# eBay1.net
KiCad netlist of a schematic drawn in EAGLE
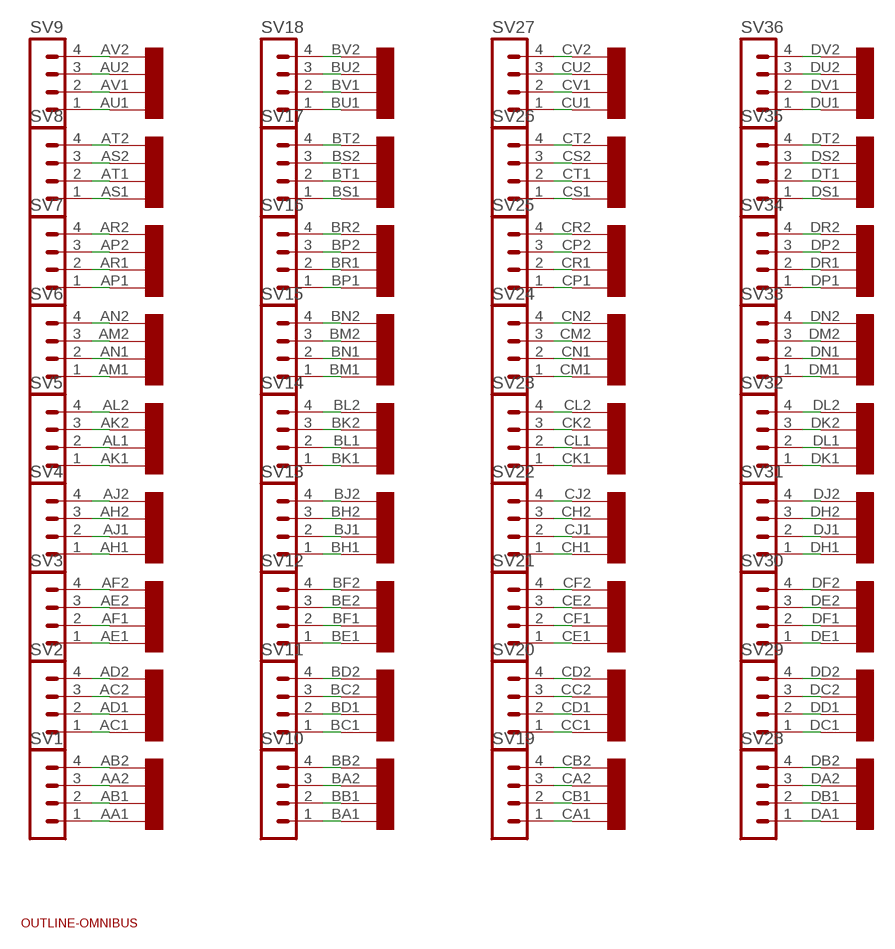
[diagram p0: schematic, sheet 1]

(export (version "E")
  (design (tool "Eeschema 10.0.6"))
  (components
    (comp (ref "SV1")
      (value "MA04-1")
      (footprint "eagle-import:MA04-1")
      (libsource (lib "eagle-import") (part "MA04-1"))
    )
    (comp (ref "SV2")
      (value "MA04-1")
      (footprint "eagle-import:MA04-1")
      (libsource (lib "eagle-import") (part "MA04-1"))
    )
    (comp (ref "SV3")
      (value "MA04-1")
      (footprint "eagle-import:MA04-1")
      (libsource (lib "eagle-import") (part "MA04-1"))
    )
    (comp (ref "SV4")
      (value "MA04-1")
      (footprint "eagle-import:MA04-1")
      (libsource (lib "eagle-import") (part "MA04-1"))
    )
    (comp (ref "SV5")
      (value "MA04-1")
      (footprint "eagle-import:MA04-1")
      (libsource (lib "eagle-import") (part "MA04-1"))
    )
    (comp (ref "SV6")
      (value "MA04-1")
      (footprint "eagle-import:MA04-1")
      (libsource (lib "eagle-import") (part "MA04-1"))
    )
    (comp (ref "SV7")
      (value "MA04-1")
      (footprint "eagle-import:MA04-1")
      (libsource (lib "eagle-import") (part "MA04-1"))
    )
    (comp (ref "SV8")
      (value "MA04-1")
      (footprint "eagle-import:MA04-1")
      (libsource (lib "eagle-import") (part "MA04-1"))
    )
    (comp (ref "SV9")
      (value "MA04-1")
      (footprint "eagle-import:MA04-1")
      (libsource (lib "eagle-import") (part "MA04-1"))
    )
    (comp (ref "SV10")
      (value "MA04-1")
      (footprint "eagle-import:MA04-1")
      (libsource (lib "eagle-import") (part "MA04-1"))
    )
    (comp (ref "SV11")
      (value "MA04-1")
      (footprint "eagle-import:MA04-1")
      (libsource (lib "eagle-import") (part "MA04-1"))
    )
    (comp (ref "SV12")
      (value "MA04-1")
      (footprint "eagle-import:MA04-1")
      (libsource (lib "eagle-import") (part "MA04-1"))
    )
    (comp (ref "SV13")
      (value "MA04-1")
      (footprint "eagle-import:MA04-1")
      (libsource (lib "eagle-import") (part "MA04-1"))
    )
    (comp (ref "SV14")
      (value "MA04-1")
      (footprint "eagle-import:MA04-1")
      (libsource (lib "eagle-import") (part "MA04-1"))
    )
    (comp (ref "SV15")
      (value "MA04-1")
      (footprint "eagle-import:MA04-1")
      (libsource (lib "eagle-import") (part "MA04-1"))
    )
    (comp (ref "SV16")
      (value "MA04-1")
      (footprint "eagle-import:MA04-1")
      (libsource (lib "eagle-import") (part "MA04-1"))
    )
    (comp (ref "SV17")
      (value "MA04-1")
      (footprint "eagle-import:MA04-1")
      (libsource (lib "eagle-import") (part "MA04-1"))
    )
    (comp (ref "SV18")
      (value "MA04-1")
      (footprint "eagle-import:MA04-1")
      (libsource (lib "eagle-import") (part "MA04-1"))
    )
    (comp (ref "SV19")
      (value "MA04-1")
      (footprint "eagle-import:MA04-1")
      (libsource (lib "eagle-import") (part "MA04-1"))
    )
    (comp (ref "SV20")
      (value "MA04-1")
      (footprint "eagle-import:MA04-1")
      (libsource (lib "eagle-import") (part "MA04-1"))
    )
    (comp (ref "SV21")
      (value "MA04-1")
      (footprint "eagle-import:MA04-1")
      (libsource (lib "eagle-import") (part "MA04-1"))
    )
    (comp (ref "SV22")
      (value "MA04-1")
      (footprint "eagle-import:MA04-1")
      (libsource (lib "eagle-import") (part "MA04-1"))
    )
    (comp (ref "SV23")
      (value "MA04-1")
      (footprint "eagle-import:MA04-1")
      (libsource (lib "eagle-import") (part "MA04-1"))
    )
    (comp (ref "SV24")
      (value "MA04-1")
      (footprint "eagle-import:MA04-1")
      (libsource (lib "eagle-import") (part "MA04-1"))
    )
    (comp (ref "SV25")
      (value "MA04-1")
      (footprint "eagle-import:MA04-1")
      (libsource (lib "eagle-import") (part "MA04-1"))
    )
    (comp (ref "SV26")
      (value "MA04-1")
      (footprint "eagle-import:MA04-1")
      (libsource (lib "eagle-import") (part "MA04-1"))
    )
    (comp (ref "SV27")
      (value "MA04-1")
      (footprint "eagle-import:MA04-1")
      (libsource (lib "eagle-import") (part "MA04-1"))
    )
    (comp (ref "SV28")
      (value "MA04-1")
      (footprint "eagle-import:MA04-1")
      (libsource (lib "eagle-import") (part "MA04-1"))
    )
    (comp (ref "SV29")
      (value "MA04-1")
      (footprint "eagle-import:MA04-1")
      (libsource (lib "eagle-import") (part "MA04-1"))
    )
    (comp (ref "SV30")
      (value "MA04-1")
      (footprint "eagle-import:MA04-1")
      (libsource (lib "eagle-import") (part "MA04-1"))
    )
    (comp (ref "SV31")
      (value "MA04-1")
      (footprint "eagle-import:MA04-1")
      (libsource (lib "eagle-import") (part "MA04-1"))
    )
    (comp (ref "SV32")
      (value "MA04-1")
      (footprint "eagle-import:MA04-1")
      (libsource (lib "eagle-import") (part "MA04-1"))
    )
    (comp (ref "SV33")
      (value "MA04-1")
      (footprint "eagle-import:MA04-1")
      (libsource (lib "eagle-import") (part "MA04-1"))
    )
    (comp (ref "SV34")
      (value "MA04-1")
      (footprint "eagle-import:MA04-1")
      (libsource (lib "eagle-import") (part "MA04-1"))
    )
    (comp (ref "SV35")
      (value "MA04-1")
      (footprint "eagle-import:MA04-1")
      (libsource (lib "eagle-import") (part "MA04-1"))
    )
    (comp (ref "SV36")
      (value "MA04-1")
      (footprint "eagle-import:MA04-1")
      (libsource (lib "eagle-import") (part "MA04-1"))
    )
    (comp (ref "U$1")
      (value "OUTLINE-OMNIBUS")
      (footprint "eagle-import:OMNIBUS")
      (libsource (lib "eagle-import") (part "OUTLINE-OMNIBUS"))
    )
    (comp (ref "U$2")
      (value "QUAD")
      (footprint "eagle-import:EDGE-CON8")
      (libsource (lib "eagle-import") (part "QUAD"))
    )
  )
  (nets
    (net (code "1") (name "Net-(U$2A-1)") (class "Default")
      (node (ref "SV1") (pin "1") (pinfunction "1_1") (pintype "passive"))
      (node (ref "U$2") (pin "AA1") (pinfunction "1_AA1") (pintype "bidirectional"))
    )
    (net (code "2") (name "Net-(U$2AA-1)") (class "Default")
      (node (ref "SV7") (pin "2") (pinfunction "2_2") (pintype "passive"))
      (node (ref "U$2") (pin "AR1") (pinfunction "1_AR1") (pintype "bidirectional"))
    )
    (net (code "3") (name "Net-(U$2AB-1)") (class "Default")
      (node (ref "SV7") (pin "4") (pinfunction "4_4") (pintype "passive"))
      (node (ref "U$2") (pin "AR2") (pinfunction "1_AR2") (pintype "bidirectional"))
    )
    (net (code "4") (name "Net-(U$2AC-1)") (class "Default")
      (node (ref "SV8") (pin "1") (pinfunction "1_1") (pintype "passive"))
      (node (ref "U$2") (pin "AS1") (pinfunction "1_AS1") (pintype "bidirectional"))
    )
    (net (code "5") (name "Net-(U$2AD-1)") (class "Default")
      (node (ref "SV8") (pin "3") (pinfunction "3_3") (pintype "passive"))
      (node (ref "U$2") (pin "AS2") (pinfunction "1_AS2") (pintype "bidirectional"))
    )
    (net (code "6") (name "Net-(U$2AE-1)") (class "Default")
      (node (ref "SV8") (pin "2") (pinfunction "2_2") (pintype "passive"))
      (node (ref "U$2") (pin "AT1") (pinfunction "1_AT1") (pintype "bidirectional"))
    )
    (net (code "7") (name "Net-(U$2AF-1)") (class "Default")
      (node (ref "SV8") (pin "4") (pinfunction "4_4") (pintype "passive"))
      (node (ref "U$2") (pin "AT2") (pinfunction "1_AT2") (pintype "bidirectional"))
    )
    (net (code "8") (name "Net-(U$2AG-1)") (class "Default")
      (node (ref "SV9") (pin "1") (pinfunction "1_1") (pintype "passive"))
      (node (ref "U$2") (pin "AU1") (pinfunction "1_AU1") (pintype "bidirectional"))
    )
    (net (code "9") (name "Net-(U$2AH-1)") (class "Default")
      (node (ref "SV9") (pin "3") (pinfunction "3_3") (pintype "passive"))
      (node (ref "U$2") (pin "AU2") (pinfunction "1_AU2") (pintype "bidirectional"))
    )
    (net (code "10") (name "Net-(U$2AI-1)") (class "Default")
      (node (ref "SV9") (pin "2") (pinfunction "2_2") (pintype "passive"))
      (node (ref "U$2") (pin "AV1") (pinfunction "1_AV1") (pintype "bidirectional"))
    )
    (net (code "11") (name "Net-(U$2AJ-1)") (class "Default")
      (node (ref "SV9") (pin "4") (pinfunction "4_4") (pintype "passive"))
      (node (ref "U$2") (pin "AV2") (pinfunction "1_AV2") (pintype "bidirectional"))
    )
    (net (code "12") (name "Net-(U$2AK-1)") (class "Default")
      (node (ref "SV10") (pin "1") (pinfunction "1_1") (pintype "passive"))
      (node (ref "U$2") (pin "BA1") (pinfunction "1_BA1") (pintype "bidirectional"))
    )
    (net (code "13") (name "Net-(U$2AL-1)") (class "Default")
      (node (ref "SV10") (pin "3") (pinfunction "3_3") (pintype "passive"))
      (node (ref "U$2") (pin "BA2") (pinfunction "1_BA2") (pintype "bidirectional"))
    )
    (net (code "14") (name "Net-(U$2AM-1)") (class "Default")
      (node (ref "SV10") (pin "2") (pinfunction "2_2") (pintype "passive"))
      (node (ref "U$2") (pin "BB1") (pinfunction "1_BB1") (pintype "bidirectional"))
    )
    (net (code "15") (name "Net-(U$2AN-1)") (class "Default")
      (node (ref "SV10") (pin "4") (pinfunction "4_4") (pintype "passive"))
      (node (ref "U$2") (pin "BB2") (pinfunction "1_BB2") (pintype "bidirectional"))
    )
    (net (code "16") (name "Net-(U$2AO-1)") (class "Default")
      (node (ref "SV11") (pin "1") (pinfunction "1_1") (pintype "passive"))
      (node (ref "U$2") (pin "BC1") (pinfunction "1_BC1") (pintype "bidirectional"))
    )
    (net (code "17") (name "Net-(U$2AP-1)") (class "Default")
      (node (ref "SV11") (pin "3") (pinfunction "3_3") (pintype "passive"))
      (node (ref "U$2") (pin "BC2") (pinfunction "1_BC2") (pintype "bidirectional"))
    )
    (net (code "18") (name "Net-(U$2AQ-1)") (class "Default")
      (node (ref "SV11") (pin "2") (pinfunction "2_2") (pintype "passive"))
      (node (ref "U$2") (pin "BD1") (pinfunction "1_BD1") (pintype "bidirectional"))
    )
    (net (code "19") (name "Net-(U$2AR-1)") (class "Default")
      (node (ref "SV11") (pin "4") (pinfunction "4_4") (pintype "passive"))
      (node (ref "U$2") (pin "BD2") (pinfunction "1_BD2") (pintype "bidirectional"))
    )
    (net (code "20") (name "Net-(U$2AS-1)") (class "Default")
      (node (ref "SV12") (pin "1") (pinfunction "1_1") (pintype "passive"))
      (node (ref "U$2") (pin "BE1") (pinfunction "1_BE1") (pintype "bidirectional"))
    )
    (net (code "21") (name "Net-(U$2AT-1)") (class "Default")
      (node (ref "SV12") (pin "3") (pinfunction "3_3") (pintype "passive"))
      (node (ref "U$2") (pin "BE2") (pinfunction "1_BE2") (pintype "bidirectional"))
    )
    (net (code "22") (name "Net-(U$2AU-1)") (class "Default")
      (node (ref "SV12") (pin "2") (pinfunction "2_2") (pintype "passive"))
      (node (ref "U$2") (pin "BF1") (pinfunction "1_BF1") (pintype "bidirectional"))
    )
    (net (code "23") (name "Net-(U$2AV-1)") (class "Default")
      (node (ref "SV12") (pin "4") (pinfunction "4_4") (pintype "passive"))
      (node (ref "U$2") (pin "BF2") (pinfunction "1_BF2") (pintype "bidirectional"))
    )
    (net (code "24") (name "Net-(U$2AW-1)") (class "Default")
      (node (ref "SV13") (pin "1") (pinfunction "1_1") (pintype "passive"))
      (node (ref "U$2") (pin "BH1") (pinfunction "1_BH1") (pintype "bidirectional"))
    )
    (net (code "25") (name "Net-(U$2AX-1)") (class "Default")
      (node (ref "SV13") (pin "3") (pinfunction "3_3") (pintype "passive"))
      (node (ref "U$2") (pin "BH2") (pinfunction "1_BH2") (pintype "bidirectional"))
    )
    (net (code "26") (name "Net-(U$2AY-1)") (class "Default")
      (node (ref "SV13") (pin "2") (pinfunction "2_2") (pintype "passive"))
      (node (ref "U$2") (pin "BJ1") (pinfunction "1_BJ1") (pintype "bidirectional"))
    )
    (net (code "27") (name "Net-(U$2AZ-1)") (class "Default")
      (node (ref "SV13") (pin "4") (pinfunction "4_4") (pintype "passive"))
      (node (ref "U$2") (pin "BJ2") (pinfunction "1_BJ2") (pintype "bidirectional"))
    )
    (net (code "28") (name "Net-(U$2B-1)") (class "Default")
      (node (ref "SV1") (pin "3") (pinfunction "3_3") (pintype "passive"))
      (node (ref "U$2") (pin "AA2") (pinfunction "1_AA2") (pintype "bidirectional"))
    )
    (net (code "29") (name "Net-(U$2BA-1)") (class "Default")
      (node (ref "SV14") (pin "1") (pinfunction "1_1") (pintype "passive"))
      (node (ref "U$2") (pin "BK1") (pinfunction "1_BK1") (pintype "bidirectional"))
    )
    (net (code "30") (name "Net-(U$2BB-1)") (class "Default")
      (node (ref "SV14") (pin "3") (pinfunction "3_3") (pintype "passive"))
      (node (ref "U$2") (pin "BK2") (pinfunction "1_BK2") (pintype "bidirectional"))
    )
    (net (code "31") (name "Net-(U$2BC-1)") (class "Default")
      (node (ref "SV14") (pin "2") (pinfunction "2_2") (pintype "passive"))
      (node (ref "U$2") (pin "BL1") (pinfunction "1_BL1") (pintype "bidirectional"))
    )
    (net (code "32") (name "Net-(U$2BD-1)") (class "Default")
      (node (ref "SV14") (pin "4") (pinfunction "4_4") (pintype "passive"))
      (node (ref "U$2") (pin "BL2") (pinfunction "1_BL2") (pintype "bidirectional"))
    )
    (net (code "33") (name "Net-(U$2BE-1)") (class "Default")
      (node (ref "SV15") (pin "1") (pinfunction "1_1") (pintype "passive"))
      (node (ref "U$2") (pin "BM1") (pinfunction "1_BM1") (pintype "bidirectional"))
    )
    (net (code "34") (name "Net-(U$2BF-1)") (class "Default")
      (node (ref "SV15") (pin "3") (pinfunction "3_3") (pintype "passive"))
      (node (ref "U$2") (pin "BM2") (pinfunction "1_BM2") (pintype "bidirectional"))
    )
    (net (code "35") (name "Net-(U$2BG-1)") (class "Default")
      (node (ref "SV15") (pin "2") (pinfunction "2_2") (pintype "passive"))
      (node (ref "U$2") (pin "BN1") (pinfunction "1_BN1") (pintype "bidirectional"))
    )
    (net (code "36") (name "Net-(U$2BH-1)") (class "Default")
      (node (ref "SV15") (pin "4") (pinfunction "4_4") (pintype "passive"))
      (node (ref "U$2") (pin "BN2") (pinfunction "1_BN2") (pintype "bidirectional"))
    )
    (net (code "37") (name "Net-(U$2BI-1)") (class "Default")
      (node (ref "SV16") (pin "1") (pinfunction "1_1") (pintype "passive"))
      (node (ref "U$2") (pin "BP1") (pinfunction "1_BP1") (pintype "bidirectional"))
    )
    (net (code "38") (name "Net-(U$2BJ-1)") (class "Default")
      (node (ref "SV16") (pin "3") (pinfunction "3_3") (pintype "passive"))
      (node (ref "U$2") (pin "BP2") (pinfunction "1_BP2") (pintype "bidirectional"))
    )
    (net (code "39") (name "Net-(U$2BK-1)") (class "Default")
      (node (ref "SV16") (pin "2") (pinfunction "2_2") (pintype "passive"))
      (node (ref "U$2") (pin "BR1") (pinfunction "1_BR1") (pintype "bidirectional"))
    )
    (net (code "40") (name "Net-(U$2BL-1)") (class "Default")
      (node (ref "SV16") (pin "4") (pinfunction "4_4") (pintype "passive"))
      (node (ref "U$2") (pin "BR2") (pinfunction "1_BR2") (pintype "bidirectional"))
    )
    (net (code "41") (name "Net-(U$2BM-1)") (class "Default")
      (node (ref "SV17") (pin "1") (pinfunction "1_1") (pintype "passive"))
      (node (ref "U$2") (pin "BS1") (pinfunction "1_BS1") (pintype "bidirectional"))
    )
    (net (code "42") (name "Net-(U$2BN-1)") (class "Default")
      (node (ref "SV17") (pin "3") (pinfunction "3_3") (pintype "passive"))
      (node (ref "U$2") (pin "BS2") (pinfunction "1_BS2") (pintype "bidirectional"))
    )
    (net (code "43") (name "Net-(U$2BO-1)") (class "Default")
      (node (ref "SV17") (pin "2") (pinfunction "2_2") (pintype "passive"))
      (node (ref "U$2") (pin "BT1") (pinfunction "1_BT1") (pintype "bidirectional"))
    )
    (net (code "44") (name "Net-(U$2BP-1)") (class "Default")
      (node (ref "SV17") (pin "4") (pinfunction "4_4") (pintype "passive"))
      (node (ref "U$2") (pin "BT2") (pinfunction "1_BT2") (pintype "bidirectional"))
    )
    (net (code "45") (name "Net-(U$2BQ-1)") (class "Default")
      (node (ref "SV18") (pin "1") (pinfunction "1_1") (pintype "passive"))
      (node (ref "U$2") (pin "BU1") (pinfunction "1_BU1") (pintype "bidirectional"))
    )
    (net (code "46") (name "Net-(U$2BR-1)") (class "Default")
      (node (ref "SV18") (pin "3") (pinfunction "3_3") (pintype "passive"))
      (node (ref "U$2") (pin "BU2") (pinfunction "1_BU2") (pintype "bidirectional"))
    )
    (net (code "47") (name "Net-(U$2BS-1)") (class "Default")
      (node (ref "SV18") (pin "2") (pinfunction "2_2") (pintype "passive"))
      (node (ref "U$2") (pin "BV1") (pinfunction "1_BV1") (pintype "bidirectional"))
    )
    (net (code "48") (name "Net-(U$2BT-1)") (class "Default")
      (node (ref "SV18") (pin "4") (pinfunction "4_4") (pintype "passive"))
      (node (ref "U$2") (pin "BV2") (pinfunction "1_BV2") (pintype "bidirectional"))
    )
    (net (code "49") (name "Net-(U$2BU-1)") (class "Default")
      (node (ref "SV19") (pin "1") (pinfunction "1_1") (pintype "passive"))
      (node (ref "U$2") (pin "CA1") (pinfunction "1_CA1") (pintype "bidirectional"))
    )
    (net (code "50") (name "Net-(U$2BV-1)") (class "Default")
      (node (ref "SV19") (pin "3") (pinfunction "3_3") (pintype "passive"))
      (node (ref "U$2") (pin "CA2") (pinfunction "1_CA2") (pintype "bidirectional"))
    )
    (net (code "51") (name "Net-(U$2BW-1)") (class "Default")
      (node (ref "SV19") (pin "2") (pinfunction "2_2") (pintype "passive"))
      (node (ref "U$2") (pin "CB1") (pinfunction "1_CB1") (pintype "bidirectional"))
    )
    (net (code "52") (name "Net-(U$2BX-1)") (class "Default")
      (node (ref "SV19") (pin "4") (pinfunction "4_4") (pintype "passive"))
      (node (ref "U$2") (pin "CB2") (pinfunction "1_CB2") (pintype "bidirectional"))
    )
    (net (code "53") (name "Net-(U$2BY-1)") (class "Default")
      (node (ref "SV20") (pin "1") (pinfunction "1_1") (pintype "passive"))
      (node (ref "U$2") (pin "CC1") (pinfunction "1_CC1") (pintype "bidirectional"))
    )
    (net (code "54") (name "Net-(U$2BZ-1)") (class "Default")
      (node (ref "SV20") (pin "3") (pinfunction "3_3") (pintype "passive"))
      (node (ref "U$2") (pin "CC2") (pinfunction "1_CC2") (pintype "bidirectional"))
    )
    (net (code "55") (name "Net-(U$2C-1)") (class "Default")
      (node (ref "SV1") (pin "2") (pinfunction "2_2") (pintype "passive"))
      (node (ref "U$2") (pin "AB1") (pinfunction "1_AB1") (pintype "bidirectional"))
    )
    (net (code "56") (name "Net-(U$2CA-1)") (class "Default")
      (node (ref "SV20") (pin "2") (pinfunction "2_2") (pintype "passive"))
      (node (ref "U$2") (pin "CD1") (pinfunction "1_CD1") (pintype "bidirectional"))
    )
    (net (code "57") (name "Net-(U$2CB-1)") (class "Default")
      (node (ref "SV20") (pin "4") (pinfunction "4_4") (pintype "passive"))
      (node (ref "U$2") (pin "CD2") (pinfunction "1_CD2") (pintype "bidirectional"))
    )
    (net (code "58") (name "Net-(U$2CC-1)") (class "Default")
      (node (ref "SV21") (pin "1") (pinfunction "1_1") (pintype "passive"))
      (node (ref "U$2") (pin "CE1") (pinfunction "1_CE1") (pintype "bidirectional"))
    )
    (net (code "59") (name "Net-(U$2CD-1)") (class "Default")
      (node (ref "SV21") (pin "3") (pinfunction "3_3") (pintype "passive"))
      (node (ref "U$2") (pin "CE2") (pinfunction "1_CE2") (pintype "bidirectional"))
    )
    (net (code "60") (name "Net-(U$2CE-1)") (class "Default")
      (node (ref "SV21") (pin "2") (pinfunction "2_2") (pintype "passive"))
      (node (ref "U$2") (pin "CF1") (pinfunction "1_CF1") (pintype "bidirectional"))
    )
    (net (code "61") (name "Net-(U$2CF-1)") (class "Default")
      (node (ref "SV21") (pin "4") (pinfunction "4_4") (pintype "passive"))
      (node (ref "U$2") (pin "CF2") (pinfunction "1_CF2") (pintype "bidirectional"))
    )
    (net (code "62") (name "Net-(U$2CG-1)") (class "Default")
      (node (ref "SV22") (pin "1") (pinfunction "1_1") (pintype "passive"))
      (node (ref "U$2") (pin "CH1") (pinfunction "1_CH1") (pintype "bidirectional"))
    )
    (net (code "63") (name "Net-(U$2CH-1)") (class "Default")
      (node (ref "SV22") (pin "3") (pinfunction "3_3") (pintype "passive"))
      (node (ref "U$2") (pin "CH2") (pinfunction "1_CH2") (pintype "bidirectional"))
    )
    (net (code "64") (name "Net-(U$2CI-1)") (class "Default")
      (node (ref "SV22") (pin "2") (pinfunction "2_2") (pintype "passive"))
      (node (ref "U$2") (pin "CJ1") (pinfunction "1_CJ1") (pintype "bidirectional"))
    )
    (net (code "65") (name "Net-(U$2CJ-1)") (class "Default")
      (node (ref "SV22") (pin "4") (pinfunction "4_4") (pintype "passive"))
      (node (ref "U$2") (pin "CJ2") (pinfunction "1_CJ2") (pintype "bidirectional"))
    )
    (net (code "66") (name "Net-(U$2CK-1)") (class "Default")
      (node (ref "SV23") (pin "1") (pinfunction "1_1") (pintype "passive"))
      (node (ref "U$2") (pin "CK1") (pinfunction "1_CK1") (pintype "bidirectional"))
    )
    (net (code "67") (name "Net-(U$2CL-1)") (class "Default")
      (node (ref "SV23") (pin "3") (pinfunction "3_3") (pintype "passive"))
      (node (ref "U$2") (pin "CK2") (pinfunction "1_CK2") (pintype "bidirectional"))
    )
    (net (code "68") (name "Net-(U$2CM-1)") (class "Default")
      (node (ref "SV23") (pin "2") (pinfunction "2_2") (pintype "passive"))
      (node (ref "U$2") (pin "CL1") (pinfunction "1_CL1") (pintype "bidirectional"))
    )
    (net (code "69") (name "Net-(U$2CN-1)") (class "Default")
      (node (ref "SV23") (pin "4") (pinfunction "4_4") (pintype "passive"))
      (node (ref "U$2") (pin "CL2") (pinfunction "1_CL2") (pintype "bidirectional"))
    )
    (net (code "70") (name "Net-(U$2CO-1)") (class "Default")
      (node (ref "SV24") (pin "1") (pinfunction "1_1") (pintype "passive"))
      (node (ref "U$2") (pin "CM1") (pinfunction "1_CM1") (pintype "bidirectional"))
    )
    (net (code "71") (name "Net-(U$2CP-1)") (class "Default")
      (node (ref "SV24") (pin "3") (pinfunction "3_3") (pintype "passive"))
      (node (ref "U$2") (pin "CM2") (pinfunction "1_CM2") (pintype "bidirectional"))
    )
    (net (code "72") (name "Net-(U$2CQ-1)") (class "Default")
      (node (ref "SV24") (pin "2") (pinfunction "2_2") (pintype "passive"))
      (node (ref "U$2") (pin "CN1") (pinfunction "1_CN1") (pintype "bidirectional"))
    )
    (net (code "73") (name "Net-(U$2CR-1)") (class "Default")
      (node (ref "SV24") (pin "4") (pinfunction "4_4") (pintype "passive"))
      (node (ref "U$2") (pin "CN2") (pinfunction "1_CN2") (pintype "bidirectional"))
    )
    (net (code "74") (name "Net-(U$2CS-1)") (class "Default")
      (node (ref "SV25") (pin "1") (pinfunction "1_1") (pintype "passive"))
      (node (ref "U$2") (pin "CP1") (pinfunction "1_CP1") (pintype "bidirectional"))
    )
    (net (code "75") (name "Net-(U$2CT-1)") (class "Default")
      (node (ref "SV25") (pin "3") (pinfunction "3_3") (pintype "passive"))
      (node (ref "U$2") (pin "CP2") (pinfunction "1_CP2") (pintype "bidirectional"))
    )
    (net (code "76") (name "Net-(U$2CU-1)") (class "Default")
      (node (ref "SV25") (pin "2") (pinfunction "2_2") (pintype "passive"))
      (node (ref "U$2") (pin "CR1") (pinfunction "1_CR1") (pintype "bidirectional"))
    )
    (net (code "77") (name "Net-(U$2CV-1)") (class "Default")
      (node (ref "SV25") (pin "4") (pinfunction "4_4") (pintype "passive"))
      (node (ref "U$2") (pin "CR2") (pinfunction "1_CR2") (pintype "bidirectional"))
    )
    (net (code "78") (name "Net-(U$2CW-1)") (class "Default")
      (node (ref "SV26") (pin "1") (pinfunction "1_1") (pintype "passive"))
      (node (ref "U$2") (pin "CS1") (pinfunction "1_CS1") (pintype "bidirectional"))
    )
    (net (code "79") (name "Net-(U$2CX-1)") (class "Default")
      (node (ref "SV26") (pin "3") (pinfunction "3_3") (pintype "passive"))
      (node (ref "U$2") (pin "CS2") (pinfunction "1_CS2") (pintype "bidirectional"))
    )
    (net (code "80") (name "Net-(U$2CY-1)") (class "Default")
      (node (ref "SV26") (pin "2") (pinfunction "2_2") (pintype "passive"))
      (node (ref "U$2") (pin "CT1") (pinfunction "1_CT1") (pintype "bidirectional"))
    )
    (net (code "81") (name "Net-(U$2CZ-1)") (class "Default")
      (node (ref "SV26") (pin "4") (pinfunction "4_4") (pintype "passive"))
      (node (ref "U$2") (pin "CT2") (pinfunction "1_CT2") (pintype "bidirectional"))
    )
    (net (code "82") (name "Net-(U$2D-1)") (class "Default")
      (node (ref "SV1") (pin "4") (pinfunction "4_4") (pintype "passive"))
      (node (ref "U$2") (pin "AB2") (pinfunction "1_AB2") (pintype "bidirectional"))
    )
    (net (code "83") (name "Net-(U$2DA-1)") (class "Default")
      (node (ref "SV27") (pin "1") (pinfunction "1_1") (pintype "passive"))
      (node (ref "U$2") (pin "CU1") (pinfunction "1_CU1") (pintype "bidirectional"))
    )
    (net (code "84") (name "Net-(U$2DB-1)") (class "Default")
      (node (ref "SV27") (pin "3") (pinfunction "3_3") (pintype "passive"))
      (node (ref "U$2") (pin "CU2") (pinfunction "1_CU2") (pintype "bidirectional"))
    )
    (net (code "85") (name "Net-(U$2DC-1)") (class "Default")
      (node (ref "SV27") (pin "2") (pinfunction "2_2") (pintype "passive"))
      (node (ref "U$2") (pin "CV1") (pinfunction "1_CV1") (pintype "bidirectional"))
    )
    (net (code "86") (name "Net-(U$2DD-1)") (class "Default")
      (node (ref "SV27") (pin "4") (pinfunction "4_4") (pintype "passive"))
      (node (ref "U$2") (pin "CV2") (pinfunction "1_CV2") (pintype "bidirectional"))
    )
    (net (code "87") (name "Net-(U$2DE-1)") (class "Default")
      (node (ref "SV28") (pin "1") (pinfunction "1_1") (pintype "passive"))
      (node (ref "U$2") (pin "DA1") (pinfunction "1_DA1") (pintype "bidirectional"))
    )
    (net (code "88") (name "Net-(U$2DF-1)") (class "Default")
      (node (ref "SV28") (pin "3") (pinfunction "3_3") (pintype "passive"))
      (node (ref "U$2") (pin "DA2") (pinfunction "1_DA2") (pintype "bidirectional"))
    )
    (net (code "89") (name "Net-(U$2DG-1)") (class "Default")
      (node (ref "SV28") (pin "2") (pinfunction "2_2") (pintype "passive"))
      (node (ref "U$2") (pin "DB1") (pinfunction "1_DB1") (pintype "bidirectional"))
    )
    (net (code "90") (name "Net-(U$2DH-1)") (class "Default")
      (node (ref "SV28") (pin "4") (pinfunction "4_4") (pintype "passive"))
      (node (ref "U$2") (pin "DB2") (pinfunction "1_DB2") (pintype "bidirectional"))
    )
    (net (code "91") (name "Net-(U$2DI-1)") (class "Default")
      (node (ref "SV29") (pin "1") (pinfunction "1_1") (pintype "passive"))
      (node (ref "U$2") (pin "DC1") (pinfunction "1_DC1") (pintype "bidirectional"))
    )
    (net (code "92") (name "Net-(U$2DJ-1)") (class "Default")
      (node (ref "SV29") (pin "3") (pinfunction "3_3") (pintype "passive"))
      (node (ref "U$2") (pin "DC2") (pinfunction "1_DC2") (pintype "bidirectional"))
    )
    (net (code "93") (name "Net-(U$2DK-1)") (class "Default")
      (node (ref "SV29") (pin "2") (pinfunction "2_2") (pintype "passive"))
      (node (ref "U$2") (pin "DD1") (pinfunction "1_DD1") (pintype "bidirectional"))
    )
    (net (code "94") (name "Net-(U$2DL-1)") (class "Default")
      (node (ref "SV29") (pin "4") (pinfunction "4_4") (pintype "passive"))
      (node (ref "U$2") (pin "DD2") (pinfunction "1_DD2") (pintype "bidirectional"))
    )
    (net (code "95") (name "Net-(U$2DM-1)") (class "Default")
      (node (ref "SV30") (pin "1") (pinfunction "1_1") (pintype "passive"))
      (node (ref "U$2") (pin "DE1") (pinfunction "1_DE1") (pintype "bidirectional"))
    )
    (net (code "96") (name "Net-(U$2DN-1)") (class "Default")
      (node (ref "SV30") (pin "3") (pinfunction "3_3") (pintype "passive"))
      (node (ref "U$2") (pin "DE2") (pinfunction "1_DE2") (pintype "bidirectional"))
    )
    (net (code "97") (name "Net-(U$2DO-1)") (class "Default")
      (node (ref "SV30") (pin "2") (pinfunction "2_2") (pintype "passive"))
      (node (ref "U$2") (pin "DF1") (pinfunction "1_DF1") (pintype "bidirectional"))
    )
    (net (code "98") (name "Net-(U$2DP-1)") (class "Default")
      (node (ref "SV30") (pin "4") (pinfunction "4_4") (pintype "passive"))
      (node (ref "U$2") (pin "DF2") (pinfunction "1_DF2") (pintype "bidirectional"))
    )
    (net (code "99") (name "Net-(U$2DQ-1)") (class "Default")
      (node (ref "SV31") (pin "1") (pinfunction "1_1") (pintype "passive"))
      (node (ref "U$2") (pin "DH1") (pinfunction "1_DH1") (pintype "bidirectional"))
    )
    (net (code "100") (name "Net-(U$2DR-1)") (class "Default")
      (node (ref "SV31") (pin "3") (pinfunction "3_3") (pintype "passive"))
      (node (ref "U$2") (pin "DH2") (pinfunction "1_DH2") (pintype "bidirectional"))
    )
    (net (code "101") (name "Net-(U$2DS-1)") (class "Default")
      (node (ref "SV31") (pin "2") (pinfunction "2_2") (pintype "passive"))
      (node (ref "U$2") (pin "DJ1") (pinfunction "1_DJ1") (pintype "bidirectional"))
    )
    (net (code "102") (name "Net-(U$2DT-1)") (class "Default")
      (node (ref "SV31") (pin "4") (pinfunction "4_4") (pintype "passive"))
      (node (ref "U$2") (pin "DJ2") (pinfunction "1_DJ2") (pintype "bidirectional"))
    )
    (net (code "103") (name "Net-(U$2DU-1)") (class "Default")
      (node (ref "SV32") (pin "1") (pinfunction "1_1") (pintype "passive"))
      (node (ref "U$2") (pin "DK1") (pinfunction "1_DK1") (pintype "bidirectional"))
    )
    (net (code "104") (name "Net-(U$2DV-1)") (class "Default")
      (node (ref "SV32") (pin "3") (pinfunction "3_3") (pintype "passive"))
      (node (ref "U$2") (pin "DK2") (pinfunction "1_DK2") (pintype "bidirectional"))
    )
    (net (code "105") (name "Net-(U$2DW-1)") (class "Default")
      (node (ref "SV32") (pin "2") (pinfunction "2_2") (pintype "passive"))
      (node (ref "U$2") (pin "DL1") (pinfunction "1_DL1") (pintype "bidirectional"))
    )
    (net (code "106") (name "Net-(U$2DX-1)") (class "Default")
      (node (ref "SV32") (pin "4") (pinfunction "4_4") (pintype "passive"))
      (node (ref "U$2") (pin "DL2") (pinfunction "1_DL2") (pintype "bidirectional"))
    )
    (net (code "107") (name "Net-(U$2DY-1)") (class "Default")
      (node (ref "SV33") (pin "1") (pinfunction "1_1") (pintype "passive"))
      (node (ref "U$2") (pin "DM1") (pinfunction "1_DM1") (pintype "bidirectional"))
    )
    (net (code "108") (name "Net-(U$2DZ-1)") (class "Default")
      (node (ref "SV33") (pin "3") (pinfunction "3_3") (pintype "passive"))
      (node (ref "U$2") (pin "DM2") (pinfunction "1_DM2") (pintype "bidirectional"))
    )
    (net (code "109") (name "Net-(U$2E-1)") (class "Default")
      (node (ref "SV2") (pin "1") (pinfunction "1_1") (pintype "passive"))
      (node (ref "U$2") (pin "AC1") (pinfunction "1_AC1") (pintype "bidirectional"))
    )
    (net (code "110") (name "Net-(U$2EA-1)") (class "Default")
      (node (ref "SV33") (pin "2") (pinfunction "2_2") (pintype "passive"))
      (node (ref "U$2") (pin "DN1") (pinfunction "1_DN1") (pintype "bidirectional"))
    )
    (net (code "111") (name "Net-(U$2EB-1)") (class "Default")
      (node (ref "SV33") (pin "4") (pinfunction "4_4") (pintype "passive"))
      (node (ref "U$2") (pin "DN2") (pinfunction "1_DN2") (pintype "bidirectional"))
    )
    (net (code "112") (name "Net-(U$2EC-1)") (class "Default")
      (node (ref "SV34") (pin "1") (pinfunction "1_1") (pintype "passive"))
      (node (ref "U$2") (pin "DP1") (pinfunction "1_DP1") (pintype "bidirectional"))
    )
    (net (code "113") (name "Net-(U$2ED-1)") (class "Default")
      (node (ref "SV34") (pin "3") (pinfunction "3_3") (pintype "passive"))
      (node (ref "U$2") (pin "DP2") (pinfunction "1_DP2") (pintype "bidirectional"))
    )
    (net (code "114") (name "Net-(U$2EE-1)") (class "Default")
      (node (ref "SV34") (pin "2") (pinfunction "2_2") (pintype "passive"))
      (node (ref "U$2") (pin "DR1") (pinfunction "1_DR1") (pintype "bidirectional"))
    )
    (net (code "115") (name "Net-(U$2EF-1)") (class "Default")
      (node (ref "SV34") (pin "4") (pinfunction "4_4") (pintype "passive"))
      (node (ref "U$2") (pin "DR2") (pinfunction "1_DR2") (pintype "bidirectional"))
    )
    (net (code "116") (name "Net-(U$2EG-1)") (class "Default")
      (node (ref "SV35") (pin "1") (pinfunction "1_1") (pintype "passive"))
      (node (ref "U$2") (pin "DS1") (pinfunction "1_DS1") (pintype "bidirectional"))
    )
    (net (code "117") (name "Net-(U$2EH-1)") (class "Default")
      (node (ref "SV35") (pin "3") (pinfunction "3_3") (pintype "passive"))
      (node (ref "U$2") (pin "DS2") (pinfunction "1_DS2") (pintype "bidirectional"))
    )
    (net (code "118") (name "Net-(U$2EI-1)") (class "Default")
      (node (ref "SV35") (pin "2") (pinfunction "2_2") (pintype "passive"))
      (node (ref "U$2") (pin "DT1") (pinfunction "1_DT1") (pintype "bidirectional"))
    )
    (net (code "119") (name "Net-(U$2EJ-1)") (class "Default")
      (node (ref "SV35") (pin "4") (pinfunction "4_4") (pintype "passive"))
      (node (ref "U$2") (pin "DT2") (pinfunction "1_DT2") (pintype "bidirectional"))
    )
    (net (code "120") (name "Net-(U$2EK-1)") (class "Default")
      (node (ref "SV36") (pin "1") (pinfunction "1_1") (pintype "passive"))
      (node (ref "U$2") (pin "DU1") (pinfunction "1_DU1") (pintype "bidirectional"))
    )
    (net (code "121") (name "Net-(U$2EL-1)") (class "Default")
      (node (ref "SV36") (pin "3") (pinfunction "3_3") (pintype "passive"))
      (node (ref "U$2") (pin "DU2") (pinfunction "1_DU2") (pintype "bidirectional"))
    )
    (net (code "122") (name "Net-(U$2EM-1)") (class "Default")
      (node (ref "SV36") (pin "2") (pinfunction "2_2") (pintype "passive"))
      (node (ref "U$2") (pin "DV1") (pinfunction "1_DV1") (pintype "bidirectional"))
    )
    (net (code "123") (name "Net-(U$2EN-1)") (class "Default")
      (node (ref "SV36") (pin "4") (pinfunction "4_4") (pintype "passive"))
      (node (ref "U$2") (pin "DV2") (pinfunction "1_DV2") (pintype "bidirectional"))
    )
    (net (code "124") (name "Net-(U$2F-1)") (class "Default")
      (node (ref "SV2") (pin "3") (pinfunction "3_3") (pintype "passive"))
      (node (ref "U$2") (pin "AC2") (pinfunction "1_AC2") (pintype "bidirectional"))
    )
    (net (code "125") (name "Net-(U$2G-1)") (class "Default")
      (node (ref "SV2") (pin "2") (pinfunction "2_2") (pintype "passive"))
      (node (ref "U$2") (pin "AD1") (pinfunction "1_AD1") (pintype "bidirectional"))
    )
    (net (code "126") (name "Net-(U$2H-1)") (class "Default")
      (node (ref "SV2") (pin "4") (pinfunction "4_4") (pintype "passive"))
      (node (ref "U$2") (pin "AD2") (pinfunction "1_AD2") (pintype "bidirectional"))
    )
    (net (code "127") (name "Net-(U$2I-1)") (class "Default")
      (node (ref "SV3") (pin "1") (pinfunction "1_1") (pintype "passive"))
      (node (ref "U$2") (pin "AE1") (pinfunction "1_AE1") (pintype "bidirectional"))
    )
    (net (code "128") (name "Net-(U$2J-1)") (class "Default")
      (node (ref "SV3") (pin "3") (pinfunction "3_3") (pintype "passive"))
      (node (ref "U$2") (pin "AE2") (pinfunction "1_AE2") (pintype "bidirectional"))
    )
    (net (code "129") (name "Net-(U$2K-1)") (class "Default")
      (node (ref "SV3") (pin "2") (pinfunction "2_2") (pintype "passive"))
      (node (ref "U$2") (pin "AF1") (pinfunction "1_AF1") (pintype "bidirectional"))
    )
    (net (code "130") (name "Net-(U$2L-1)") (class "Default")
      (node (ref "SV3") (pin "4") (pinfunction "4_4") (pintype "passive"))
      (node (ref "U$2") (pin "AF2") (pinfunction "1_AF2") (pintype "bidirectional"))
    )
    (net (code "131") (name "Net-(U$2M-1)") (class "Default")
      (node (ref "SV4") (pin "1") (pinfunction "1_1") (pintype "passive"))
      (node (ref "U$2") (pin "AH1") (pinfunction "1_AH1") (pintype "bidirectional"))
    )
    (net (code "132") (name "Net-(U$2N-1)") (class "Default")
      (node (ref "SV4") (pin "3") (pinfunction "3_3") (pintype "passive"))
      (node (ref "U$2") (pin "AH2") (pinfunction "1_AH2") (pintype "bidirectional"))
    )
    (net (code "133") (name "Net-(U$2O-1)") (class "Default")
      (node (ref "SV4") (pin "2") (pinfunction "2_2") (pintype "passive"))
      (node (ref "U$2") (pin "AJ1") (pinfunction "1_AJ1") (pintype "bidirectional"))
    )
    (net (code "134") (name "Net-(U$2P-1)") (class "Default")
      (node (ref "SV4") (pin "4") (pinfunction "4_4") (pintype "passive"))
      (node (ref "U$2") (pin "AJ2") (pinfunction "1_AJ2") (pintype "bidirectional"))
    )
    (net (code "135") (name "Net-(U$2Q-1)") (class "Default")
      (node (ref "SV5") (pin "1") (pinfunction "1_1") (pintype "passive"))
      (node (ref "U$2") (pin "AK1") (pinfunction "1_AK1") (pintype "bidirectional"))
    )
    (net (code "136") (name "Net-(U$2R-1)") (class "Default")
      (node (ref "SV5") (pin "3") (pinfunction "3_3") (pintype "passive"))
      (node (ref "U$2") (pin "AK2") (pinfunction "1_AK2") (pintype "bidirectional"))
    )
    (net (code "137") (name "Net-(U$2S-1)") (class "Default")
      (node (ref "SV5") (pin "2") (pinfunction "2_2") (pintype "passive"))
      (node (ref "U$2") (pin "AL1") (pinfunction "1_AL1") (pintype "bidirectional"))
    )
    (net (code "138") (name "Net-(U$2T-1)") (class "Default")
      (node (ref "SV5") (pin "4") (pinfunction "4_4") (pintype "passive"))
      (node (ref "U$2") (pin "AL2") (pinfunction "1_AL2") (pintype "bidirectional"))
    )
    (net (code "139") (name "Net-(U$2U-1)") (class "Default")
      (node (ref "SV6") (pin "1") (pinfunction "1_1") (pintype "passive"))
      (node (ref "U$2") (pin "AM1") (pinfunction "1_AM1") (pintype "bidirectional"))
    )
    (net (code "140") (name "Net-(U$2V-1)") (class "Default")
      (node (ref "SV6") (pin "3") (pinfunction "3_3") (pintype "passive"))
      (node (ref "U$2") (pin "AM2") (pinfunction "1_AM2") (pintype "bidirectional"))
    )
    (net (code "141") (name "Net-(U$2W-1)") (class "Default")
      (node (ref "SV6") (pin "2") (pinfunction "2_2") (pintype "passive"))
      (node (ref "U$2") (pin "AN1") (pinfunction "1_AN1") (pintype "bidirectional"))
    )
    (net (code "142") (name "Net-(U$2X-1)") (class "Default")
      (node (ref "SV6") (pin "4") (pinfunction "4_4") (pintype "passive"))
      (node (ref "U$2") (pin "AN2") (pinfunction "1_AN2") (pintype "bidirectional"))
    )
    (net (code "143") (name "Net-(U$2Y-1)") (class "Default")
      (node (ref "SV7") (pin "1") (pinfunction "1_1") (pintype "passive"))
      (node (ref "U$2") (pin "AP1") (pinfunction "1_AP1") (pintype "bidirectional"))
    )
    (net (code "144") (name "Net-(U$2Z-1)") (class "Default")
      (node (ref "SV7") (pin "3") (pinfunction "3_3") (pintype "passive"))
      (node (ref "U$2") (pin "AP2") (pinfunction "1_AP2") (pintype "bidirectional"))
    )
  )
)
